# Bell.net
KiCad netlist of a schematic drawn in EAGLE
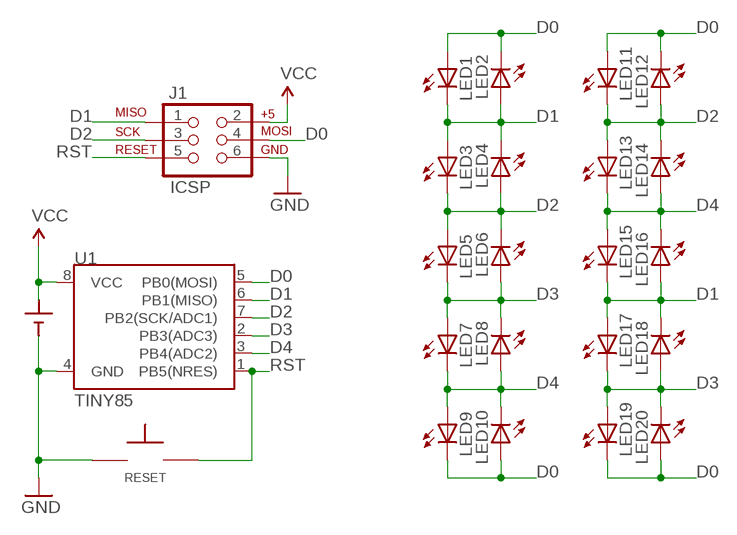
[diagram p0: schematic, sheet 1]

(export (version "E")
  (design (tool "Eeschema 10.0.6"))
  (components
    (comp (ref "BATT")
      (value "CR2032")
      (footprint "eagle-import:CR2032-THRU")
      (libsource (lib "eagle-import") (part "BATTCR2032_THRU"))
    )
    (comp (ref "J1")
      (value "ICSP")
      (footprint "eagle-import:2X3-NS")
      (libsource (lib "eagle-import") (part "AVR_SPI_PRG_6LABELED"))
    )
    (comp (ref "LED1")
      (value "LED5MM")
      (footprint "eagle-import:LED5MM")
      (libsource (lib "eagle-import") (part "LED5MM"))
    )
    (comp (ref "LED2")
      (value "LED5MM")
      (footprint "eagle-import:LED5MM")
      (libsource (lib "eagle-import") (part "LED5MM"))
    )
    (comp (ref "LED3")
      (value "LED5MM")
      (footprint "eagle-import:LED5MM")
      (libsource (lib "eagle-import") (part "LED5MM"))
    )
    (comp (ref "LED4")
      (value "LED5MM")
      (footprint "eagle-import:LED5MM")
      (libsource (lib "eagle-import") (part "LED5MM"))
    )
    (comp (ref "LED5")
      (value "LED5MM")
      (footprint "eagle-import:LED5MM")
      (libsource (lib "eagle-import") (part "LED5MM"))
    )
    (comp (ref "LED6")
      (value "LED5MM")
      (footprint "eagle-import:LED5MM")
      (libsource (lib "eagle-import") (part "LED5MM"))
    )
    (comp (ref "LED7")
      (value "LED5MM")
      (footprint "eagle-import:LED5MM")
      (libsource (lib "eagle-import") (part "LED5MM"))
    )
    (comp (ref "LED8")
      (value "LED5MM")
      (footprint "eagle-import:LED5MM")
      (libsource (lib "eagle-import") (part "LED5MM"))
    )
    (comp (ref "LED9")
      (value "LED5MM")
      (footprint "eagle-import:LED5MM")
      (libsource (lib "eagle-import") (part "LED5MM"))
    )
    (comp (ref "LED10")
      (value "LED5MM")
      (footprint "eagle-import:LED5MM")
      (libsource (lib "eagle-import") (part "LED5MM"))
    )
    (comp (ref "LED11")
      (value "LED5MM")
      (footprint "eagle-import:LED5MM")
      (libsource (lib "eagle-import") (part "LED5MM"))
    )
    (comp (ref "LED12")
      (value "LED5MM")
      (footprint "eagle-import:LED5MM")
      (libsource (lib "eagle-import") (part "LED5MM"))
    )
    (comp (ref "LED13")
      (value "LED5MM")
      (footprint "eagle-import:LED5MM")
      (libsource (lib "eagle-import") (part "LED5MM"))
    )
    (comp (ref "LED14")
      (value "LED5MM")
      (footprint "eagle-import:LED5MM")
      (libsource (lib "eagle-import") (part "LED5MM"))
    )
    (comp (ref "LED15")
      (value "LED5MM")
      (footprint "eagle-import:LED5MM")
      (libsource (lib "eagle-import") (part "LED5MM"))
    )
    (comp (ref "LED16")
      (value "LED5MM")
      (footprint "eagle-import:LED5MM")
      (libsource (lib "eagle-import") (part "LED5MM"))
    )
    (comp (ref "LED17")
      (value "LED5MM")
      (footprint "eagle-import:LED5MM")
      (libsource (lib "eagle-import") (part "LED5MM"))
    )
    (comp (ref "LED18")
      (value "LED5MM")
      (footprint "eagle-import:LED5MM")
      (libsource (lib "eagle-import") (part "LED5MM"))
    )
    (comp (ref "LED19")
      (value "LED5MM")
      (footprint "eagle-import:LED5MM")
      (libsource (lib "eagle-import") (part "LED5MM"))
    )
    (comp (ref "LED20")
      (value "LED5MM")
      (footprint "eagle-import:LED5MM")
      (libsource (lib "eagle-import") (part "LED5MM"))
    )
    (comp (ref "RESET")
      (value "TAC_SPST_NO")
      (footprint "eagle-import:TAC_SPST_NO")
      (libsource (lib "eagle-import") (part "TAC_SPST_NO"))
    )
    (comp (ref "U1")
      (value "TINY85")
      (footprint "eagle-import:DIP08")
      (libsource (lib "eagle-import") (part "ATTINY45TINY85-20-DIP"))
    )
  )
  (nets
    (net (code "1") (name "/D0") (class "Default")
      (node (ref "J1") (pin "4") (pinfunction "MOSI_4") (pintype "passive"))
      (node (ref "LED1") (pin "A") (pinfunction "A_A") (pintype "passive"))
      (node (ref "LED10") (pin "A") (pinfunction "A_A") (pintype "passive"))
      (node (ref "LED11") (pin "A") (pinfunction "A_A") (pintype "passive"))
      (node (ref "LED12") (pin "K") (pinfunction "C_K") (pintype "passive"))
      (node (ref "LED19") (pin "K") (pinfunction "C_K") (pintype "passive"))
      (node (ref "LED2") (pin "K") (pinfunction "C_K") (pintype "passive"))
      (node (ref "LED20") (pin "A") (pinfunction "A_A") (pintype "passive"))
      (node (ref "LED9") (pin "K") (pinfunction "C_K") (pintype "passive"))
      (node (ref "U1") (pin "5") (pinfunction "PB0(MOSI)_5") (pintype "bidirectional"))
    )
    (net (code "2") (name "/D1") (class "Default")
      (node (ref "J1") (pin "1") (pinfunction "MISO_1") (pintype "passive"))
      (node (ref "LED1") (pin "K") (pinfunction "C_K") (pintype "passive"))
      (node (ref "LED15") (pin "K") (pinfunction "C_K") (pintype "passive"))
      (node (ref "LED16") (pin "A") (pinfunction "A_A") (pintype "passive"))
      (node (ref "LED17") (pin "A") (pinfunction "A_A") (pintype "passive"))
      (node (ref "LED18") (pin "K") (pinfunction "C_K") (pintype "passive"))
      (node (ref "LED2") (pin "A") (pinfunction "A_A") (pintype "passive"))
      (node (ref "LED3") (pin "A") (pinfunction "A_A") (pintype "passive"))
      (node (ref "LED4") (pin "K") (pinfunction "C_K") (pintype "passive"))
      (node (ref "U1") (pin "6") (pinfunction "PB1(MISO)_6") (pintype "bidirectional"))
    )
    (net (code "3") (name "/D2") (class "Default")
      (node (ref "J1") (pin "3") (pinfunction "SCK_3") (pintype "passive"))
      (node (ref "LED11") (pin "K") (pinfunction "C_K") (pintype "passive"))
      (node (ref "LED12") (pin "A") (pinfunction "A_A") (pintype "passive"))
      (node (ref "LED13") (pin "A") (pinfunction "A_A") (pintype "passive"))
      (node (ref "LED14") (pin "K") (pinfunction "C_K") (pintype "passive"))
      (node (ref "LED3") (pin "K") (pinfunction "C_K") (pintype "passive"))
      (node (ref "LED4") (pin "A") (pinfunction "A_A") (pintype "passive"))
      (node (ref "LED5") (pin "A") (pinfunction "A_A") (pintype "passive"))
      (node (ref "LED6") (pin "K") (pinfunction "C_K") (pintype "passive"))
      (node (ref "U1") (pin "7") (pinfunction "PB2(SCK/ADC1)_7") (pintype "bidirectional"))
    )
    (net (code "4") (name "/D3") (class "Default")
      (node (ref "LED17") (pin "K") (pinfunction "C_K") (pintype "passive"))
      (node (ref "LED18") (pin "A") (pinfunction "A_A") (pintype "passive"))
      (node (ref "LED19") (pin "A") (pinfunction "A_A") (pintype "passive"))
      (node (ref "LED20") (pin "K") (pinfunction "C_K") (pintype "passive"))
      (node (ref "LED5") (pin "K") (pinfunction "C_K") (pintype "passive"))
      (node (ref "LED6") (pin "A") (pinfunction "A_A") (pintype "passive"))
      (node (ref "LED7") (pin "A") (pinfunction "A_A") (pintype "passive"))
      (node (ref "LED8") (pin "K") (pinfunction "C_K") (pintype "passive"))
      (node (ref "U1") (pin "2") (pinfunction "PB3(ADC3)_2") (pintype "bidirectional"))
    )
    (net (code "5") (name "/D4") (class "Default")
      (node (ref "LED10") (pin "K") (pinfunction "C_K") (pintype "passive"))
      (node (ref "LED13") (pin "K") (pinfunction "C_K") (pintype "passive"))
      (node (ref "LED14") (pin "A") (pinfunction "A_A") (pintype "passive"))
      (node (ref "LED15") (pin "A") (pinfunction "A_A") (pintype "passive"))
      (node (ref "LED16") (pin "K") (pinfunction "C_K") (pintype "passive"))
      (node (ref "LED7") (pin "K") (pinfunction "C_K") (pintype "passive"))
      (node (ref "LED8") (pin "A") (pinfunction "A_A") (pintype "passive"))
      (node (ref "LED9") (pin "A") (pinfunction "A_A") (pintype "passive"))
      (node (ref "U1") (pin "3") (pinfunction "PB4(ADC2)_3") (pintype "bidirectional"))
    )
    (net (code "6") (name "/RST") (class "Default")
      (node (ref "J1") (pin "5") (pinfunction "RST_5") (pintype "passive"))
      (node (ref "RESET") (pin "P$2") (pinfunction "P$2_P$2") (pintype "bidirectional"))
      (node (ref "U1") (pin "1") (pinfunction "PB5(NRES)_1") (pintype "bidirectional"))
    )
    (net (code "7") (name "GND") (class "Default")
      (node (ref "BATT") (pin "-") (pinfunction "-_-") (pintype "power_in"))
      (node (ref "J1") (pin "6") (pinfunction "GND_6") (pintype "passive"))
      (node (ref "RESET") (pin "P$1") (pinfunction "P$1_P$1") (pintype "bidirectional"))
      (node (ref "U1") (pin "4") (pinfunction "GND_4") (pintype "bidirectional"))
    )
    (net (code "8") (name "VCC") (class "Default")
      (node (ref "BATT") (pin "+1") (pinfunction "+_+1") (pintype "power_in"))
      (node (ref "J1") (pin "2") (pinfunction "V+_2") (pintype "passive"))
      (node (ref "U1") (pin "8") (pinfunction "VCC_8") (pintype "bidirectional"))
    )
  )
)
